# untitled.net
KiCad netlist of a schematic drawn in EAGLE
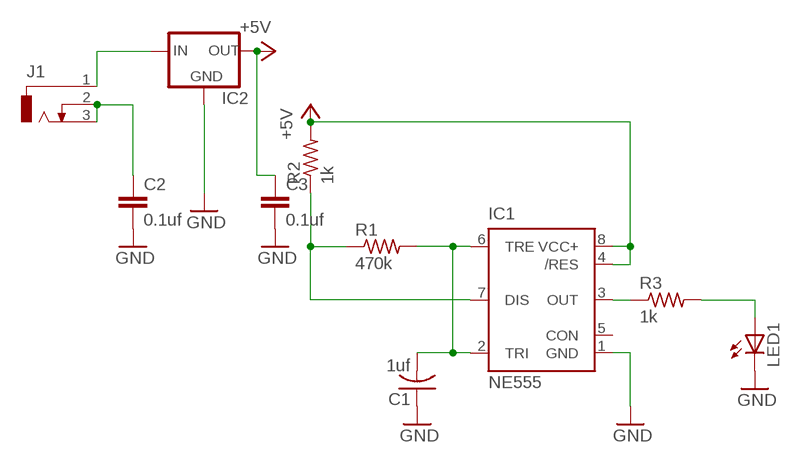
[diagram p0: schematic, sheet 1]

(export (version "E")
  (design (tool "Eeschema 10.0.6"))
  (components
    (comp (ref "C1")
      (value "1uf")
      (footprint "eagle-import:C025-024X044")
      (libsource (lib "eagle-import") (part "C-US025-024X044"))
    )
    (comp (ref "C2")
      (value "0.1uf")
      (footprint "eagle-import:C025-030X050")
      (libsource (lib "eagle-import") (part "C-EU025-030X050"))
    )
    (comp (ref "C3")
      (value "0.1uf")
      (footprint "eagle-import:C025-030X050")
      (libsource (lib "eagle-import") (part "C-EU025-030X050"))
    )
    (comp (ref "IC1")
      (value "NE555")
      (footprint "eagle-import:DIL-08")
      (fields (field (name "MF") "Arrow Electronics") (field (name "MPN") "NE555N"))
      (libsource (lib "eagle-import") (part "NE555"))
    )
    (comp (ref "IC2")
      (value "78XXS")
      (footprint "eagle-import:78XXS")
      (libsource (lib "eagle-import") (part "78XXS"))
    )
    (comp (ref "J1")
      (value "DCJ0303")
      (footprint "eagle-import:DCJ0303")
      (libsource (lib "eagle-import") (part "DCJ0303"))
    )
    (comp (ref "LED1")
      (value "LED5MM")
      (footprint "eagle-import:LED5MM")
      (libsource (lib "eagle-import") (part "LED5MM"))
    )
    (comp (ref "R1")
      (value "470k")
      (footprint "eagle-import:0309_12")
      (libsource (lib "eagle-import") (part "R-US_0309/12"))
    )
    (comp (ref "R2")
      (value "1k")
      (footprint "eagle-import:0309_12")
      (libsource (lib "eagle-import") (part "R-US_0309/12"))
    )
    (comp (ref "R3")
      (value "1k")
      (footprint "eagle-import:0309_12")
      (libsource (lib "eagle-import") (part "R-US_0309/12"))
    )
  )
  (nets
    (net (code "1") (name "+5V") (class "Default")
      (node (ref "C3") (pin "1") (pinfunction "1_1") (pintype "passive"))
      (node (ref "IC1") (pin "4") (pinfunction "/RES_4") (pintype "input"))
      (node (ref "IC1") (pin "8") (pinfunction "VCC+_8") (pintype "power_in"))
      (node (ref "IC2") (pin "OUT") (pinfunction "OUT_OUT") (pintype "passive"))
      (node (ref "R2") (pin "2") (pinfunction "2_2") (pintype "passive"))
    )
    (net (code "2") (name "GND") (class "Default")
      (node (ref "C1") (pin "1") (pinfunction "1_1") (pintype "passive"))
      (node (ref "C2") (pin "2") (pinfunction "2_2") (pintype "passive"))
      (node (ref "C3") (pin "2") (pinfunction "2_2") (pintype "passive"))
      (node (ref "IC1") (pin "1") (pinfunction "GND_1") (pintype "power_in"))
      (node (ref "IC2") (pin "GND") (pinfunction "GND_GND") (pintype "input"))
      (node (ref "LED1") (pin "K") (pinfunction "C_K") (pintype "passive"))
    )
    (net (code "3") (name "Net-(C2-Pad1)") (class "Default")
      (node (ref "C2") (pin "1") (pinfunction "1_1") (pintype "passive"))
      (node (ref "J1") (pin "2") (pinfunction "2_2") (pintype "passive"))
      (node (ref "J1") (pin "3") (pinfunction "3_3") (pintype "passive"))
    )
    (net (code "4") (name "Net-(IC1-DIS)") (class "Default")
      (node (ref "IC1") (pin "7") (pinfunction "DIS_7") (pintype "input"))
      (node (ref "R1") (pin "1") (pinfunction "1_1") (pintype "passive"))
      (node (ref "R2") (pin "1") (pinfunction "1_1") (pintype "passive"))
    )
    (net (code "5") (name "Net-(IC1-OUT)") (class "Default")
      (node (ref "IC1") (pin "3") (pinfunction "OUT_3") (pintype "output"))
      (node (ref "R3") (pin "1") (pinfunction "1_1") (pintype "passive"))
    )
    (net (code "6") (name "Net-(IC1-TRE)") (class "Default")
      (node (ref "C1") (pin "2") (pinfunction "2_2") (pintype "passive"))
      (node (ref "IC1") (pin "2") (pinfunction "TRI_2") (pintype "input"))
      (node (ref "IC1") (pin "6") (pinfunction "TRE_6") (pintype "input"))
      (node (ref "R1") (pin "2") (pinfunction "2_2") (pintype "passive"))
    )
    (net (code "7") (name "Net-(IC2-PadIN)") (class "Default")
      (node (ref "IC2") (pin "IN") (pinfunction "IN_IN") (pintype "input"))
      (node (ref "J1") (pin "1") (pinfunction "1_1") (pintype "passive"))
    )
    (net (code "8") (name "Net-(LED1-PadA)") (class "Default")
      (node (ref "LED1") (pin "A") (pinfunction "A_A") (pintype "passive"))
      (node (ref "R3") (pin "2") (pinfunction "2_2") (pintype "passive"))
    )
    (net (code "9") (name "unconnected-(IC1-CON-Pad5)") (class "Default")
      (node (ref "IC1") (pin "5") (pinfunction "CON_5") (pintype "input"))
    )
  )
)
